# Pi-Can-Hat.net
KiCad netlist of a schematic drawn in EAGLE
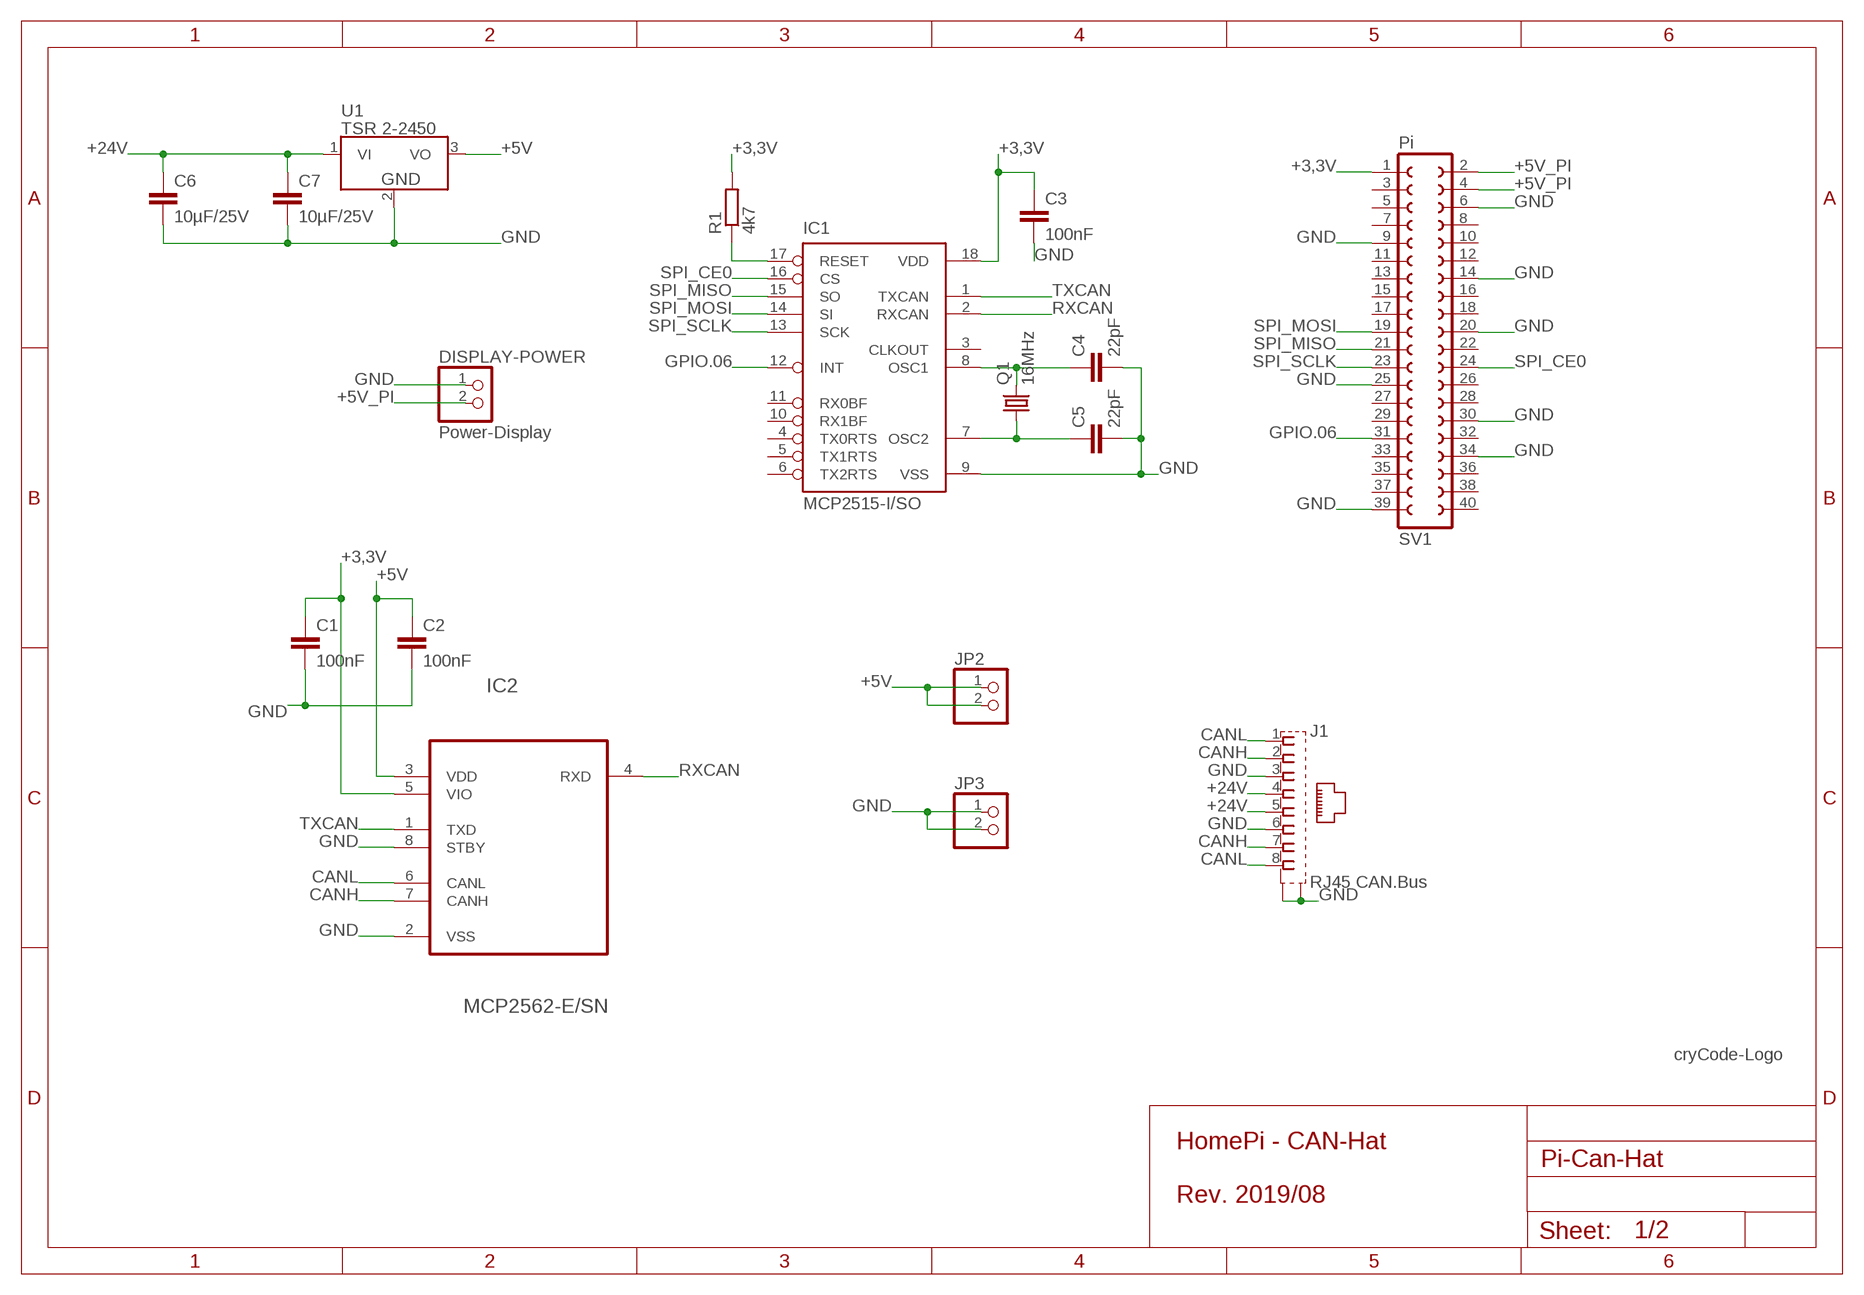
[diagram p0: schematic, sheet 1]
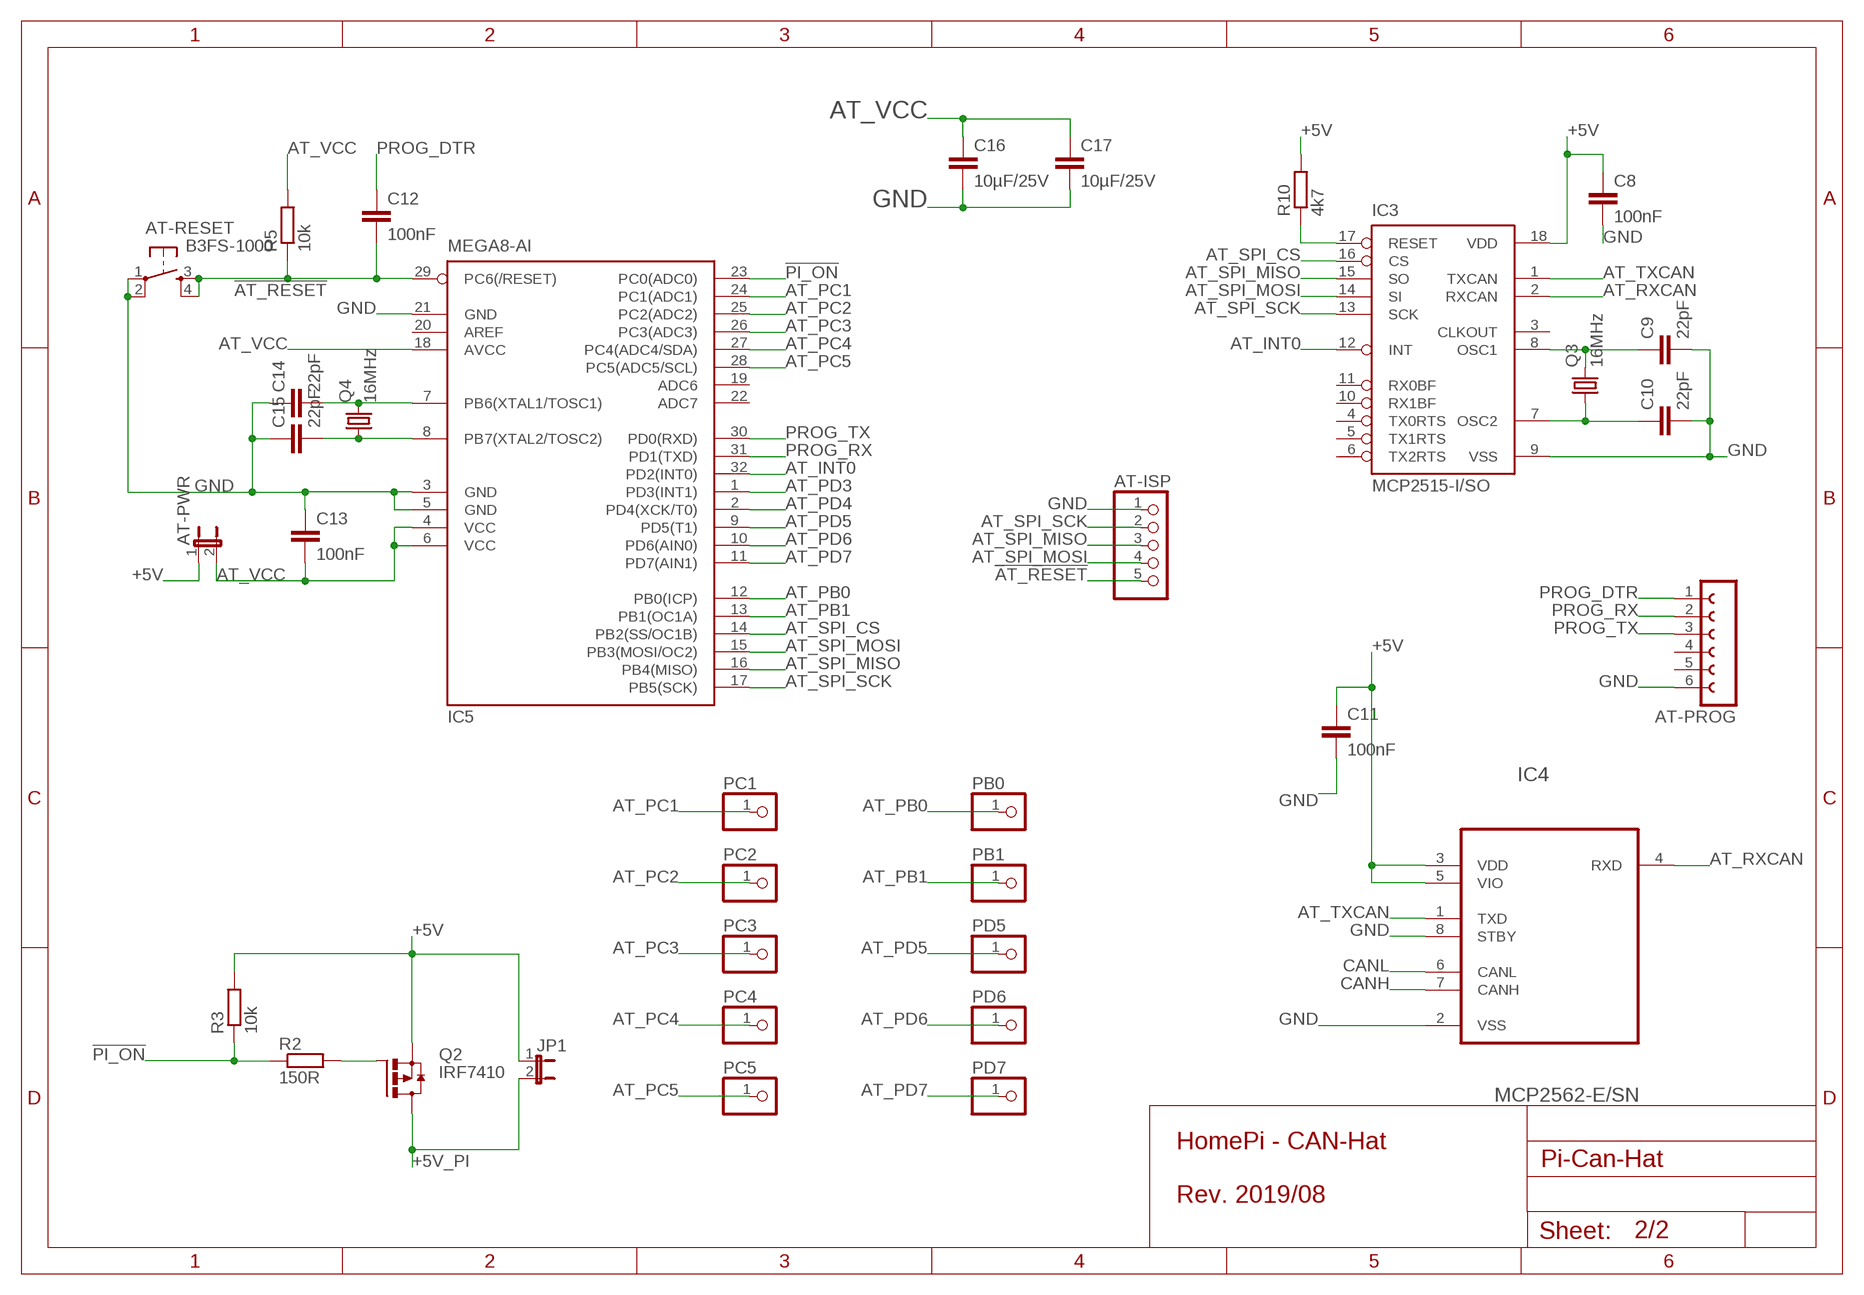
[diagram p1: schematic, sheet 2]

(export (version "E")
  (design (tool "Eeschema 10.0.6"))
  (components
    (comp (ref "AT-ISP")
      (value "PINHD-1X5")
      (footprint "eagle-import:1X05")
      (libsource (lib "eagle-import") (part "PINHD-1X5"))
    )
    (comp (ref "AT-PROG")
      (value "FE06W")
      (footprint "eagle-import:FE06W")
      (libsource (lib "eagle-import") (part "FE06W"))
    )
    (comp (ref "AT-PWR")
      (value "JP1E")
      (footprint "eagle-import:JP1")
      (libsource (lib "eagle-import") (part "JP1E"))
    )
    (comp (ref "AT-RESET")
      (value "B3FS-1000")
      (footprint "eagle-import:B3FS-1000")
      (libsource (lib "eagle-import") (part "B3FS-1000"))
    )
    (comp (ref "C8")
      (value "100nF")
      (footprint "eagle-import:C1206")
      (libsource (lib "eagle-import") (part "C-EUC1206"))
    )
    (comp (ref "C9")
      (value "22pF")
      (footprint "eagle-import:C1206")
      (libsource (lib "eagle-import") (part "C-EUC1206"))
    )
    (comp (ref "C10")
      (value "22pF")
      (footprint "eagle-import:C1206")
      (libsource (lib "eagle-import") (part "C-EUC1206"))
    )
    (comp (ref "C11")
      (value "100nF")
      (footprint "eagle-import:C1206")
      (libsource (lib "eagle-import") (part "C-EUC1206"))
    )
    (comp (ref "C12")
      (value "100nF")
      (footprint "eagle-import:C1206")
      (libsource (lib "eagle-import") (part "C-EUC1206"))
    )
    (comp (ref "C13")
      (value "100nF")
      (footprint "eagle-import:C1206")
      (libsource (lib "eagle-import") (part "C-EUC1206"))
    )
    (comp (ref "C14")
      (value "22pF")
      (footprint "eagle-import:C1206")
      (libsource (lib "eagle-import") (part "C-EUC1206"))
    )
    (comp (ref "C15")
      (value "22pF")
      (footprint "eagle-import:C1206")
      (libsource (lib "eagle-import") (part "C-EUC1206"))
    )
    (comp (ref "C16")
      (value "10µF/25V")
      (footprint "eagle-import:C1206")
      (libsource (lib "eagle-import") (part "C-EUC1206"))
    )
    (comp (ref "C17")
      (value "10µF/25V")
      (footprint "eagle-import:C1206")
      (libsource (lib "eagle-import") (part "C-EUC1206"))
    )
    (comp (ref "IC3")
      (value "MCP2515-I/SO")
      (footprint "eagle-import:SO18L")
      (libsource (lib "eagle-import") (part "MCP2515-I/SO"))
    )
    (comp (ref "IC4")
      (value "MCP2562-E/SN")
      (footprint "eagle-import:SO08")
      (libsource (lib "eagle-import") (part "MCP2562-E/SN"))
    )
    (comp (ref "IC5")
      (value "MEGA8-AI")
      (footprint "eagle-import:TQFP32-08")
      (fields (field (name "MPN") "ATMEGA8-16AU"))
      (libsource (lib "eagle-import") (part "MEGA8-AI"))
    )
    (comp (ref "JP1")
      (value "JP1E")
      (footprint "eagle-import:JP1")
      (libsource (lib "eagle-import") (part "JP1E"))
    )
    (comp (ref "PB0")
      (value "PINHD-1X1")
      (footprint "eagle-import:1X01")
      (libsource (lib "eagle-import") (part "PINHD-1X1"))
    )
    (comp (ref "PB1")
      (value "PINHD-1X1")
      (footprint "eagle-import:1X01")
      (libsource (lib "eagle-import") (part "PINHD-1X1"))
    )
    (comp (ref "PC1")
      (value "PINHD-1X1")
      (footprint "eagle-import:1X01")
      (libsource (lib "eagle-import") (part "PINHD-1X1"))
    )
    (comp (ref "PC2")
      (value "PINHD-1X1")
      (footprint "eagle-import:1X01")
      (libsource (lib "eagle-import") (part "PINHD-1X1"))
    )
    (comp (ref "PC3")
      (value "PINHD-1X1")
      (footprint "eagle-import:1X01")
      (libsource (lib "eagle-import") (part "PINHD-1X1"))
    )
    (comp (ref "PC4")
      (value "PINHD-1X1")
      (footprint "eagle-import:1X01")
      (libsource (lib "eagle-import") (part "PINHD-1X1"))
    )
    (comp (ref "PC5")
      (value "PINHD-1X1")
      (footprint "eagle-import:1X01")
      (libsource (lib "eagle-import") (part "PINHD-1X1"))
    )
    (comp (ref "PD5")
      (value "PINHD-1X1")
      (footprint "eagle-import:1X01")
      (libsource (lib "eagle-import") (part "PINHD-1X1"))
    )
    (comp (ref "PD6")
      (value "PINHD-1X1")
      (footprint "eagle-import:1X01")
      (libsource (lib "eagle-import") (part "PINHD-1X1"))
    )
    (comp (ref "PD7")
      (value "PINHD-1X1")
      (footprint "eagle-import:1X01")
      (libsource (lib "eagle-import") (part "PINHD-1X1"))
    )
    (comp (ref "Q2")
      (value "IRF7410")
      (footprint "eagle-import:SO08")
      (libsource (lib "eagle-import") (part "IRF7410"))
    )
    (comp (ref "Q3")
      (value "16MHz")
      (footprint "eagle-import:HC49UP")
      (libsource (lib "eagle-import") (part "CRYSTALHC49UP"))
    )
    (comp (ref "Q4")
      (value "16MHz")
      (footprint "eagle-import:HC49UP")
      (libsource (lib "eagle-import") (part "CRYSTALHC49UP"))
    )
    (comp (ref "R2")
      (value "150R")
      (footprint "eagle-import:R1206")
      (libsource (lib "eagle-import") (part "R-EU_R1206"))
    )
    (comp (ref "R3")
      (value "10k")
      (footprint "eagle-import:R1206")
      (libsource (lib "eagle-import") (part "R-EU_R1206"))
    )
    (comp (ref "R5")
      (value "10k")
      (footprint "eagle-import:R1206")
      (libsource (lib "eagle-import") (part "R-EU_R1206"))
    )
    (comp (ref "R10")
      (value "4k7")
      (footprint "eagle-import:R1206")
      (libsource (lib "eagle-import") (part "R-EU_R1206"))
    )
    (comp (ref "C1")
      (value "100nF")
      (footprint "eagle-import:C1206")
      (libsource (lib "eagle-import") (part "C-EUC1206"))
    )
    (comp (ref "C2")
      (value "100nF")
      (footprint "eagle-import:C1206")
      (libsource (lib "eagle-import") (part "C-EUC1206"))
    )
    (comp (ref "C3")
      (value "100nF")
      (footprint "eagle-import:C1206")
      (libsource (lib "eagle-import") (part "C-EUC1206"))
    )
    (comp (ref "C4")
      (value "22pF")
      (footprint "eagle-import:C1206")
      (libsource (lib "eagle-import") (part "C-EUC1206"))
    )
    (comp (ref "C5")
      (value "22pF")
      (footprint "eagle-import:C1206")
      (libsource (lib "eagle-import") (part "C-EUC1206"))
    )
    (comp (ref "C6")
      (value "10µF/25V")
      (footprint "eagle-import:C1206")
      (libsource (lib "eagle-import") (part "C-EUC1206"))
    )
    (comp (ref "C7")
      (value "10µF/25V")
      (footprint "eagle-import:C1206")
      (libsource (lib "eagle-import") (part "C-EUC1206"))
    )
    (comp (ref "DISPLAY-POWER")
      (value "Power-Display")
      (footprint "eagle-import:1X02_90")
      (libsource (lib "eagle-import") (part "PINHD-1X2/90"))
    )
    (comp (ref "IC1")
      (value "MCP2515-I/SO")
      (footprint "eagle-import:SO18L")
      (libsource (lib "eagle-import") (part "MCP2515-I/SO"))
    )
    (comp (ref "IC2")
      (value "MCP2562-E/SN")
      (footprint "eagle-import:SO08")
      (libsource (lib "eagle-import") (part "MCP2562-E/SN"))
    )
    (comp (ref "J1")
      (value "RJ45 CAN.Bus")
      (footprint "eagle-import:MEBP_8-8G")
      (libsource (lib "eagle-import") (part "555141-1"))
    )
    (comp (ref "JP2")
      (value "PINHD-1X2")
      (footprint "eagle-import:1X02")
      (libsource (lib "eagle-import") (part "PINHD-1X2"))
    )
    (comp (ref "JP3")
      (value "PINHD-1X2")
      (footprint "eagle-import:1X02")
      (libsource (lib "eagle-import") (part "PINHD-1X2"))
    )
    (comp (ref "Q1")
      (value "16MHz")
      (footprint "eagle-import:HC49UP")
      (libsource (lib "eagle-import") (part "CRYSTALHC49UP"))
    )
    (comp (ref "R1")
      (value "4k7")
      (footprint "eagle-import:R1206")
      (libsource (lib "eagle-import") (part "R-EU_R1206"))
    )
    (comp (ref "SV1")
      (value "Pi")
      (footprint "eagle-import:FE20-2")
      (libsource (lib "eagle-import") (part "FE20-2"))
    )
    (comp (ref "U$1")
      (value "LOGO30MM")
      (footprint "eagle-import:30MM")
      (libsource (lib "eagle-import") (part "LOGO30MM"))
    )
    (comp (ref "U1")
      (value "TSR 2-2450")
      (footprint "eagle-import:TSR2")
      (libsource (lib "eagle-import") (part "TSR2-2450"))
    )
  )
  (nets
    (net (code "1") (name "+3,3V") (class "Default")
      (node (ref "C1") (pin "1") (pinfunction "1_1") (pintype "passive"))
      (node (ref "C3") (pin "1") (pinfunction "1_1") (pintype "passive"))
      (node (ref "IC1") (pin "18") (pinfunction "VDD_18") (pintype "power_in"))
      (node (ref "IC2") (pin "5") (pinfunction "VIO_5") (pintype "power_in"))
      (node (ref "R1") (pin "2") (pinfunction "2_2") (pintype "passive"))
      (node (ref "SV1") (pin "1") (pinfunction "1_1") (pintype "passive"))
    )
    (net (code "2") (name "+5V") (class "Default")
      (node (ref "AT-PWR") (pin "1") (pinfunction "1_1") (pintype "passive"))
      (node (ref "C11") (pin "1") (pinfunction "1_1") (pintype "passive"))
      (node (ref "C2") (pin "1") (pinfunction "1_1") (pintype "passive"))
      (node (ref "C8") (pin "1") (pinfunction "1_1") (pintype "passive"))
      (node (ref "IC2") (pin "3") (pinfunction "VDD_3") (pintype "power_in"))
      (node (ref "IC3") (pin "18") (pinfunction "VDD_18") (pintype "power_in"))
      (node (ref "IC4") (pin "3") (pinfunction "VDD_3") (pintype "power_in"))
      (node (ref "IC4") (pin "5") (pinfunction "VIO_5") (pintype "power_in"))
      (node (ref "JP1") (pin "1") (pinfunction "1_1") (pintype "passive"))
      (node (ref "JP2") (pin "1") (pinfunction "1_1") (pintype "passive"))
      (node (ref "JP2") (pin "2") (pinfunction "2_2") (pintype "passive"))
      (node (ref "Q2") (pin "1") (pinfunction "S_1") (pintype "passive"))
      (node (ref "Q2") (pin "2") (pinfunction "S_2") (pintype "passive"))
      (node (ref "Q2") (pin "3") (pinfunction "S_3") (pintype "passive"))
      (node (ref "R10") (pin "2") (pinfunction "2_2") (pintype "passive"))
      (node (ref "R3") (pin "2") (pinfunction "2_2") (pintype "passive"))
      (node (ref "U1") (pin "3") (pinfunction "VO_3") (pintype "power_in"))
    )
    (net (code "3") (name "+5V_PI") (class "Default")
      (node (ref "DISPLAY-POWER") (pin "2") (pinfunction "2_2") (pintype "passive"))
      (node (ref "JP1") (pin "2") (pinfunction "2_2") (pintype "passive"))
      (node (ref "Q2") (pin "5") (pinfunction "D_5") (pintype "passive"))
      (node (ref "Q2") (pin "6") (pinfunction "D_6") (pintype "passive"))
      (node (ref "Q2") (pin "7") (pinfunction "D_7") (pintype "passive"))
      (node (ref "Q2") (pin "8") (pinfunction "D_8") (pintype "passive"))
      (node (ref "SV1") (pin "2") (pinfunction "2_2") (pintype "passive"))
      (node (ref "SV1") (pin "4") (pinfunction "4_4") (pintype "passive"))
    )
    (net (code "4") (name "+24V") (class "Default")
      (node (ref "C6") (pin "1") (pinfunction "1_1") (pintype "passive"))
      (node (ref "C7") (pin "1") (pinfunction "1_1") (pintype "passive"))
      (node (ref "J1") (pin "4") (pinfunction "4_4") (pintype "passive"))
      (node (ref "J1") (pin "5") (pinfunction "5_5") (pintype "passive"))
      (node (ref "U1") (pin "1") (pinfunction "VI_1") (pintype "power_in"))
    )
    (net (code "5") (name "AT_INT0") (class "Default")
      (node (ref "IC3") (pin "12") (pinfunction "INT_12") (pintype "output"))
      (node (ref "IC5") (pin "32") (pinfunction "PD2(INT0)_32") (pintype "bidirectional"))
    )
    (net (code "6") (name "AT_PB0") (class "Default")
      (node (ref "IC5") (pin "12") (pinfunction "PB0(ICP)_12") (pintype "bidirectional"))
      (node (ref "PB0") (pin "1") (pinfunction "1_1") (pintype "passive"))
    )
    (net (code "7") (name "AT_PB1") (class "Default")
      (node (ref "IC5") (pin "13") (pinfunction "PB1(OC1A)_13") (pintype "bidirectional"))
      (node (ref "PB1") (pin "1") (pinfunction "1_1") (pintype "passive"))
    )
    (net (code "8") (name "AT_PC1") (class "Default")
      (node (ref "IC5") (pin "24") (pinfunction "PC1(ADC1)_24") (pintype "bidirectional"))
      (node (ref "PC1") (pin "1") (pinfunction "1_1") (pintype "passive"))
    )
    (net (code "9") (name "AT_PC2") (class "Default")
      (node (ref "IC5") (pin "25") (pinfunction "PC2(ADC2)_25") (pintype "bidirectional"))
      (node (ref "PC2") (pin "1") (pinfunction "1_1") (pintype "passive"))
    )
    (net (code "10") (name "AT_PC3") (class "Default")
      (node (ref "IC5") (pin "26") (pinfunction "PC3(ADC3)_26") (pintype "bidirectional"))
      (node (ref "PC3") (pin "1") (pinfunction "1_1") (pintype "passive"))
    )
    (net (code "11") (name "AT_PC4") (class "Default")
      (node (ref "IC5") (pin "27") (pinfunction "PC4(ADC4/SDA)_27") (pintype "bidirectional"))
      (node (ref "PC4") (pin "1") (pinfunction "1_1") (pintype "passive"))
    )
    (net (code "12") (name "AT_PC5") (class "Default")
      (node (ref "IC5") (pin "28") (pinfunction "PC5(ADC5/SCL)_28") (pintype "bidirectional"))
      (node (ref "PC5") (pin "1") (pinfunction "1_1") (pintype "passive"))
    )
    (net (code "13") (name "AT_PD3") (class "Default")
      (node (ref "IC5") (pin "1") (pinfunction "PD3(INT1)_1") (pintype "bidirectional"))
    )
    (net (code "14") (name "AT_PD4") (class "Default")
      (node (ref "IC5") (pin "2") (pinfunction "PD4(XCK/T0)_2") (pintype "bidirectional"))
    )
    (net (code "15") (name "AT_PD5") (class "Default")
      (node (ref "IC5") (pin "9") (pinfunction "PD5(T1)_9") (pintype "bidirectional"))
      (node (ref "PD5") (pin "1") (pinfunction "1_1") (pintype "passive"))
    )
    (net (code "16") (name "AT_PD6") (class "Default")
      (node (ref "IC5") (pin "10") (pinfunction "PD6(AIN0)_10") (pintype "bidirectional"))
      (node (ref "PD6") (pin "1") (pinfunction "1_1") (pintype "passive"))
    )
    (net (code "17") (name "AT_PD7") (class "Default")
      (node (ref "IC5") (pin "11") (pinfunction "PD7(AIN1)_11") (pintype "bidirectional"))
      (node (ref "PD7") (pin "1") (pinfunction "1_1") (pintype "passive"))
    )
    (net (code "18") (name "AT_RXCAN") (class "Default")
      (node (ref "IC3") (pin "2") (pinfunction "RXCAN_2") (pintype "input"))
      (node (ref "IC4") (pin "4") (pinfunction "RXD_4") (pintype "output"))
    )
    (net (code "19") (name "AT_SPI_CS") (class "Default")
      (node (ref "IC3") (pin "16") (pinfunction "CS_16") (pintype "input"))
      (node (ref "IC5") (pin "14") (pinfunction "PB2(SS/OC1B)_14") (pintype "bidirectional"))
    )
    (net (code "20") (name "AT_SPI_MISO") (class "Default")
      (node (ref "AT-ISP") (pin "3") (pinfunction "3_3") (pintype "passive"))
      (node (ref "IC3") (pin "15") (pinfunction "SO_15") (pintype "output"))
      (node (ref "IC5") (pin "16") (pinfunction "PB4(MISO)_16") (pintype "bidirectional"))
    )
    (net (code "21") (name "AT_SPI_MOSI") (class "Default")
      (node (ref "AT-ISP") (pin "4") (pinfunction "4_4") (pintype "passive"))
      (node (ref "IC3") (pin "14") (pinfunction "SI_14") (pintype "input"))
      (node (ref "IC5") (pin "15") (pinfunction "PB3(MOSI/OC2)_15") (pintype "bidirectional"))
    )
    (net (code "22") (name "AT_SPI_SCK") (class "Default")
      (node (ref "AT-ISP") (pin "2") (pinfunction "2_2") (pintype "passive"))
      (node (ref "IC3") (pin "13") (pinfunction "SCK_13") (pintype "input"))
      (node (ref "IC5") (pin "17") (pinfunction "PB5(SCK)_17") (pintype "bidirectional"))
    )
    (net (code "23") (name "AT_TXCAN") (class "Default")
      (node (ref "IC3") (pin "1") (pinfunction "TXCAN_1") (pintype "output"))
      (node (ref "IC4") (pin "1") (pinfunction "TXD_1") (pintype "input"))
    )
    (net (code "24") (name "AT_VCC") (class "Default")
      (node (ref "AT-PWR") (pin "2") (pinfunction "2_2") (pintype "passive"))
      (node (ref "C13") (pin "2") (pinfunction "2_2") (pintype "passive"))
      (node (ref "C16") (pin "1") (pinfunction "1_1") (pintype "passive"))
      (node (ref "C17") (pin "1") (pinfunction "1_1") (pintype "passive"))
      (node (ref "IC5") (pin "18") (pinfunction "AVCC_18") (pintype "power_in"))
      (node (ref "IC5") (pin "4") (pinfunction "VCC_4") (pintype "power_in"))
      (node (ref "IC5") (pin "6") (pinfunction "VCC_6") (pintype "power_in"))
      (node (ref "R5") (pin "2") (pinfunction "2_2") (pintype "passive"))
    )
    (net (code "25") (name "CANH") (class "Default")
      (node (ref "IC2") (pin "7") (pinfunction "CANH_7") (pintype "bidirectional"))
      (node (ref "IC4") (pin "7") (pinfunction "CANH_7") (pintype "bidirectional"))
      (node (ref "J1") (pin "2") (pinfunction "2_2") (pintype "passive"))
      (node (ref "J1") (pin "7") (pinfunction "7_7") (pintype "passive"))
    )
    (net (code "26") (name "CANL") (class "Default")
      (node (ref "IC2") (pin "6") (pinfunction "CANL_6") (pintype "bidirectional"))
      (node (ref "IC4") (pin "6") (pinfunction "CANL_6") (pintype "bidirectional"))
      (node (ref "J1") (pin "1") (pinfunction "1_1") (pintype "passive"))
      (node (ref "J1") (pin "8") (pinfunction "8_8") (pintype "passive"))
    )
    (net (code "27") (name "GND") (class "Default")
      (node (ref "AT-ISP") (pin "1") (pinfunction "1_1") (pintype "passive"))
      (node (ref "AT-PROG") (pin "6") (pinfunction "6_6") (pintype "passive"))
      (node (ref "AT-RESET") (pin "1") (pinfunction "P_1") (pintype "passive"))
      (node (ref "AT-RESET") (pin "2") (pinfunction "P1_2") (pintype "passive"))
      (node (ref "C1") (pin "2") (pinfunction "2_2") (pintype "passive"))
      (node (ref "C10") (pin "2") (pinfunction "2_2") (pintype "passive"))
      (node (ref "C11") (pin "2") (pinfunction "2_2") (pintype "passive"))
      (node (ref "C13") (pin "1") (pinfunction "1_1") (pintype "passive"))
      (node (ref "C14") (pin "1") (pinfunction "1_1") (pintype "passive"))
      (node (ref "C15") (pin "1") (pinfunction "1_1") (pintype "passive"))
      (node (ref "C16") (pin "2") (pinfunction "2_2") (pintype "passive"))
      (node (ref "C17") (pin "2") (pinfunction "2_2") (pintype "passive"))
      (node (ref "C2") (pin "2") (pinfunction "2_2") (pintype "passive"))
      (node (ref "C3") (pin "2") (pinfunction "2_2") (pintype "passive"))
      (node (ref "C4") (pin "2") (pinfunction "2_2") (pintype "passive"))
      (node (ref "C5") (pin "2") (pinfunction "2_2") (pintype "passive"))
      (node (ref "C6") (pin "2") (pinfunction "2_2") (pintype "passive"))
      (node (ref "C7") (pin "2") (pinfunction "2_2") (pintype "passive"))
      (node (ref "C8") (pin "2") (pinfunction "2_2") (pintype "passive"))
      (node (ref "C9") (pin "2") (pinfunction "2_2") (pintype "passive"))
      (node (ref "DISPLAY-POWER") (pin "1") (pinfunction "1_1") (pintype "passive"))
      (node (ref "IC1") (pin "9") (pinfunction "VSS_9") (pintype "power_in"))
      (node (ref "IC2") (pin "2") (pinfunction "VSS_2") (pintype "power_in"))
      (node (ref "IC2") (pin "8") (pinfunction "STBY_8") (pintype "input"))
      (node (ref "IC3") (pin "9") (pinfunction "VSS_9") (pintype "power_in"))
      (node (ref "IC4") (pin "2") (pinfunction "VSS_2") (pintype "power_in"))
      (node (ref "IC4") (pin "8") (pinfunction "STBY_8") (pintype "input"))
      (node (ref "IC5") (pin "21") (pinfunction "GND_21") (pintype "power_in"))
      (node (ref "IC5") (pin "3") (pinfunction "GND_3") (pintype "power_in"))
      (node (ref "IC5") (pin "5") (pinfunction "GND_5") (pintype "power_in"))
      (node (ref "J1") (pin "3") (pinfunction "3_3") (pintype "passive"))
      (node (ref "J1") (pin "6") (pinfunction "6_6") (pintype "passive"))
      (node (ref "J1") (pin "G1") (pinfunction "S1_G1") (pintype "passive"))
      (node (ref "J1") (pin "G2") (pinfunction "S2_G2") (pintype "passive"))
      (node (ref "JP3") (pin "1") (pinfunction "1_1") (pintype "passive"))
      (node (ref "JP3") (pin "2") (pinfunction "2_2") (pintype "passive"))
      (node (ref "SV1") (pin "14") (pinfunction "14_14") (pintype "passive"))
      (node (ref "SV1") (pin "20") (pinfunction "20_20") (pintype "passive"))
      (node (ref "SV1") (pin "25") (pinfunction "25_25") (pintype "passive"))
      (node (ref "SV1") (pin "30") (pinfunction "30_30") (pintype "passive"))
      (node (ref "SV1") (pin "34") (pinfunction "34_34") (pintype "passive"))
      (node (ref "SV1") (pin "39") (pinfunction "39_39") (pintype "passive"))
      (node (ref "SV1") (pin "6") (pinfunction "6_6") (pintype "passive"))
      (node (ref "SV1") (pin "9") (pinfunction "9_9") (pintype "passive"))
      (node (ref "U1") (pin "2") (pinfunction "GND_2") (pintype "power_in"))
    )
    (net (code "28") (name "GPIO.06") (class "Default")
      (node (ref "IC1") (pin "12") (pinfunction "INT_12") (pintype "output"))
      (node (ref "SV1") (pin "31") (pinfunction "31_31") (pintype "passive"))
    )
    (net (code "29") (name "Net-(IC1-OSC1)") (class "Default")
      (node (ref "C4") (pin "1") (pinfunction "1_1") (pintype "passive"))
      (node (ref "IC1") (pin "8") (pinfunction "OSC1_8") (pintype "input"))
      (node (ref "Q1") (pin "2") (pinfunction "2_2") (pintype "passive"))
    )
    (net (code "30") (name "Net-(IC1-OSC2)") (class "Default")
      (node (ref "C5") (pin "1") (pinfunction "1_1") (pintype "passive"))
      (node (ref "IC1") (pin "7") (pinfunction "OSC2_7") (pintype "output"))
      (node (ref "Q1") (pin "1") (pinfunction "1_1") (pintype "passive"))
    )
    (net (code "31") (name "Net-(IC1-RESET)") (class "Default")
      (node (ref "IC1") (pin "17") (pinfunction "RESET_17") (pintype "input"))
      (node (ref "R1") (pin "1") (pinfunction "1_1") (pintype "passive"))
    )
    (net (code "32") (name "Net-(IC3-OSC1)") (class "Default")
      (node (ref "C9") (pin "1") (pinfunction "1_1") (pintype "passive"))
      (node (ref "IC3") (pin "8") (pinfunction "OSC1_8") (pintype "input"))
      (node (ref "Q3") (pin "2") (pinfunction "2_2") (pintype "passive"))
    )
    (net (code "33") (name "Net-(IC3-OSC2)") (class "Default")
      (node (ref "C10") (pin "1") (pinfunction "1_1") (pintype "passive"))
      (node (ref "IC3") (pin "7") (pinfunction "OSC2_7") (pintype "output"))
      (node (ref "Q3") (pin "1") (pinfunction "1_1") (pintype "passive"))
    )
    (net (code "34") (name "Net-(IC3-RESET)") (class "Default")
      (node (ref "IC3") (pin "17") (pinfunction "RESET_17") (pintype "input"))
      (node (ref "R10") (pin "1") (pinfunction "1_1") (pintype "passive"))
    )
    (net (code "35") (name "Net-(IC5-PB6(XTAL1{slash}TOSC1))") (class "Default")
      (node (ref "C14") (pin "2") (pinfunction "2_2") (pintype "passive"))
      (node (ref "IC5") (pin "7") (pinfunction "PB6(XTAL1/TOSC1)_7") (pintype "bidirectional"))
      (node (ref "Q4") (pin "2") (pinfunction "2_2") (pintype "passive"))
    )
    (net (code "36") (name "Net-(IC5-PB7(XTAL2{slash}TOSC2))") (class "Default")
      (node (ref "C15") (pin "2") (pinfunction "2_2") (pintype "passive"))
      (node (ref "IC5") (pin "8") (pinfunction "PB7(XTAL2/TOSC2)_8") (pintype "bidirectional"))
      (node (ref "Q4") (pin "1") (pinfunction "1_1") (pintype "passive"))
    )
    (net (code "37") (name "Net-(Q2-G)") (class "Default")
      (node (ref "Q2") (pin "4") (pinfunction "G_4") (pintype "passive"))
      (node (ref "R2") (pin "2") (pinfunction "2_2") (pintype "passive"))
    )
    (net (code "38") (name "PROG_DTR") (class "Default")
      (node (ref "AT-PROG") (pin "1") (pinfunction "1_1") (pintype "passive"))
      (node (ref "C12") (pin "1") (pinfunction "1_1") (pintype "passive"))
    )
    (net (code "39") (name "PROG_RX") (class "Default")
      (node (ref "AT-PROG") (pin "2") (pinfunction "2_2") (pintype "passive"))
      (node (ref "IC5") (pin "31") (pinfunction "PD1(TXD)_31") (pintype "bidirectional"))
    )
    (net (code "40") (name "PROG_TX") (class "Default")
      (node (ref "AT-PROG") (pin "3") (pinfunction "3_3") (pintype "passive"))
      (node (ref "IC5") (pin "30") (pinfunction "PD0(RXD)_30") (pintype "bidirectional"))
    )
    (net (code "41") (name "RXCAN") (class "Default")
      (node (ref "IC1") (pin "2") (pinfunction "RXCAN_2") (pintype "input"))
      (node (ref "IC2") (pin "4") (pinfunction "RXD_4") (pintype "output"))
    )
    (net (code "42") (name "SPI_CE0") (class "Default")
      (node (ref "IC1") (pin "16") (pinfunction "CS_16") (pintype "input"))
      (node (ref "SV1") (pin "24") (pinfunction "24_24") (pintype "passive"))
    )
    (net (code "43") (name "SPI_MISO") (class "Default")
      (node (ref "IC1") (pin "15") (pinfunction "SO_15") (pintype "output"))
      (node (ref "SV1") (pin "21") (pinfunction "21_21") (pintype "passive"))
    )
    (net (code "44") (name "SPI_MOSI") (class "Default")
      (node (ref "IC1") (pin "14") (pinfunction "SI_14") (pintype "input"))
      (node (ref "SV1") (pin "19") (pinfunction "19_19") (pintype "passive"))
    )
    (net (code "45") (name "SPI_SCLK") (class "Default")
      (node (ref "IC1") (pin "13") (pinfunction "SCK_13") (pintype "input"))
      (node (ref "SV1") (pin "23") (pinfunction "23_23") (pintype "passive"))
    )
    (net (code "46") (name "TXCAN") (class "Default")
      (node (ref "IC1") (pin "1") (pinfunction "TXCAN_1") (pintype "output"))
      (node (ref "IC2") (pin "1") (pinfunction "TXD_1") (pintype "input"))
    )
    (net (code "47") (name "unconnected-(AT-PROG-Pad4)") (class "Default")
      (node (ref "AT-PROG") (pin "4") (pinfunction "4_4") (pintype "passive"))
    )
    (net (code "48") (name "unconnected-(AT-PROG-Pad5)") (class "Default")
      (node (ref "AT-PROG") (pin "5") (pinfunction "5_5") (pintype "passive"))
    )
    (net (code "49") (name "unconnected-(IC1-CLKOUT-Pad3)") (class "Default")
      (node (ref "IC1") (pin "3") (pinfunction "CLKOUT_3") (pintype "output"))
    )
    (net (code "50") (name "unconnected-(IC1-RX0BF-Pad11)") (class "Default")
      (node (ref "IC1") (pin "11") (pinfunction "RX0BF_11") (pintype "output"))
    )
    (net (code "51") (name "unconnected-(IC1-RX1BF-Pad10)") (class "Default")
      (node (ref "IC1") (pin "10") (pinfunction "RX1BF_10") (pintype "output"))
    )
    (net (code "52") (name "unconnected-(IC1-TX0RTS-Pad4)") (class "Default")
      (node (ref "IC1") (pin "4") (pinfunction "TX0RTS_4") (pintype "input"))
    )
    (net (code "53") (name "unconnected-(IC1-TX1RTS-Pad5)") (class "Default")
      (node (ref "IC1") (pin "5") (pinfunction "TX1RTS_5") (pintype "input"))
    )
    (net (code "54") (name "unconnected-(IC1-TX2RTS-Pad6)") (class "Default")
      (node (ref "IC1") (pin "6") (pinfunction "TX2RTS_6") (pintype "input"))
    )
    (net (code "55") (name "unconnected-(IC3-CLKOUT-Pad3)") (class "Default")
      (node (ref "IC3") (pin "3") (pinfunction "CLKOUT_3") (pintype "output"))
    )
    (net (code "56") (name "unconnected-(IC3-RX0BF-Pad11)") (class "Default")
      (node (ref "IC3") (pin "11") (pinfunction "RX0BF_11") (pintype "output"))
    )
    (net (code "57") (name "unconnected-(IC3-RX1BF-Pad10)") (class "Default")
      (node (ref "IC3") (pin "10") (pinfunction "RX1BF_10") (pintype "output"))
    )
    (net (code "58") (name "unconnected-(IC3-TX0RTS-Pad4)") (class "Default")
      (node (ref "IC3") (pin "4") (pinfunction "TX0RTS_4") (pintype "input"))
    )
    (net (code "59") (name "unconnected-(IC3-TX1RTS-Pad5)") (class "Default")
      (node (ref "IC3") (pin "5") (pinfunction "TX1RTS_5") (pintype "input"))
    )
    (net (code "60") (name "unconnected-(IC3-TX2RTS-Pad6)") (class "Default")
      (node (ref "IC3") (pin "6") (pinfunction "TX2RTS_6") (pintype "input"))
    )
    (net (code "61") (name "unconnected-(IC5-ADC6-Pad19)") (class "Default")
      (node (ref "IC5") (pin "19") (pinfunction "ADC6_19") (pintype "bidirectional"))
    )
    (net (code "62") (name "unconnected-(IC5-ADC7-Pad22)") (class "Default")
      (node (ref "IC5") (pin "22") (pinfunction "ADC7_22") (pintype "bidirectional"))
    )
    (net (code "63") (name "unconnected-(IC5-AREF-Pad20)") (class "Default")
      (node (ref "IC5") (pin "20") (pinfunction "AREF_20") (pintype "passive"))
    )
    (net (code "64") (name "unconnected-(SV1-Pad3)") (class "Default")
      (node (ref "SV1") (pin "3") (pinfunction "3_3") (pintype "passive"))
    )
    (net (code "65") (name "unconnected-(SV1-Pad5)") (class "Default")
      (node (ref "SV1") (pin "5") (pinfunction "5_5") (pintype "passive"))
    )
    (net (code "66") (name "unconnected-(SV1-Pad7)") (class "Default")
      (node (ref "SV1") (pin "7") (pinfunction "7_7") (pintype "passive"))
    )
    (net (code "67") (name "unconnected-(SV1-Pad8)") (class "Default")
      (node (ref "SV1") (pin "8") (pinfunction "8_8") (pintype "passive"))
    )
    (net (code "68") (name "unconnected-(SV1-Pad10)") (class "Default")
      (node (ref "SV1") (pin "10") (pinfunction "10_10") (pintype "passive"))
    )
    (net (code "69") (name "unconnected-(SV1-Pad11)") (class "Default")
      (node (ref "SV1") (pin "11") (pinfunction "11_11") (pintype "passive"))
    )
    (net (code "70") (name "unconnected-(SV1-Pad12)") (class "Default")
      (node (ref "SV1") (pin "12") (pinfunction "12_12") (pintype "passive"))
    )
    (net (code "71") (name "unconnected-(SV1-Pad13)") (class "Default")
      (node (ref "SV1") (pin "13") (pinfunction "13_13") (pintype "passive"))
    )
    (net (code "72") (name "unconnected-(SV1-Pad15)") (class "Default")
      (node (ref "SV1") (pin "15") (pinfunction "15_15") (pintype "passive"))
    )
    (net (code "73") (name "unconnected-(SV1-Pad16)") (class "Default")
      (node (ref "SV1") (pin "16") (pinfunction "16_16") (pintype "passive"))
    )
    (net (code "74") (name "unconnected-(SV1-Pad17)") (class "Default")
      (node (ref "SV1") (pin "17") (pinfunction "17_17") (pintype "passive"))
    )
    (net (code "75") (name "unconnected-(SV1-Pad18)") (class "Default")
      (node (ref "SV1") (pin "18") (pinfunction "18_18") (pintype "passive"))
    )
    (net (code "76") (name "unconnected-(SV1-Pad22)") (class "Default")
      (node (ref "SV1") (pin "22") (pinfunction "22_22") (pintype "passive"))
    )
    (net (code "77") (name "unconnected-(SV1-Pad26)") (class "Default")
      (node (ref "SV1") (pin "26") (pinfunction "26_26") (pintype "passive"))
    )
    (net (code "78") (name "unconnected-(SV1-Pad27)") (class "Default")
      (node (ref "SV1") (pin "27") (pinfunction "27_27") (pintype "passive"))
    )
    (net (code "79") (name "unconnected-(SV1-Pad28)") (class "Default")
      (node (ref "SV1") (pin "28") (pinfunction "28_28") (pintype "passive"))
    )
    (net (code "80") (name "unconnected-(SV1-Pad29)") (class "Default")
      (node (ref "SV1") (pin "29") (pinfunction "29_29") (pintype "passive"))
    )
    (net (code "81") (name "unconnected-(SV1-Pad32)") (class "Default")
      (node (ref "SV1") (pin "32") (pinfunction "32_32") (pintype "passive"))
    )
    (net (code "82") (name "unconnected-(SV1-Pad33)") (class "Default")
      (node (ref "SV1") (pin "33") (pinfunction "33_33") (pintype "passive"))
    )
    (net (code "83") (name "unconnected-(SV1-Pad35)") (class "Default")
      (node (ref "SV1") (pin "35") (pinfunction "35_35") (pintype "passive"))
    )
    (net (code "84") (name "unconnected-(SV1-Pad36)") (class "Default")
      (node (ref "SV1") (pin "36") (pinfunction "36_36") (pintype "passive"))
    )
    (net (code "85") (name "unconnected-(SV1-Pad37)") (class "Default")
      (node (ref "SV1") (pin "37") (pinfunction "37_37") (pintype "passive"))
    )
    (net (code "86") (name "unconnected-(SV1-Pad38)") (class "Default")
      (node (ref "SV1") (pin "38") (pinfunction "38_38") (pintype "passive"))
    )
    (net (code "87") (name "unconnected-(SV1-Pad40)") (class "Default")
      (node (ref "SV1") (pin "40") (pinfunction "40_40") (pintype "passive"))
    )
    (net (code "88") (name "~{AT_RESET}") (class "Default")
      (node (ref "AT-ISP") (pin "5") (pinfunction "5_5") (pintype "passive"))
      (node (ref "AT-RESET") (pin "3") (pinfunction "S_3") (pintype "passive"))
      (node (ref "AT-RESET") (pin "4") (pinfunction "S1_4") (pintype "passive"))
      (node (ref "C12") (pin "2") (pinfunction "2_2") (pintype "passive"))
      (node (ref "IC5") (pin "29") (pinfunction "PC6(/RESET)_29") (pintype "bidirectional"))
      (node (ref "R5") (pin "1") (pinfunction "1_1") (pintype "passive"))
    )
    (net (code "89") (name "~{PI_ON}") (class "Default")
      (node (ref "IC5") (pin "23") (pinfunction "PC0(ADC0)_23") (pintype "bidirectional"))
      (node (ref "R2") (pin "1") (pinfunction "1_1") (pintype "passive"))
      (node (ref "R3") (pin "1") (pinfunction "1_1") (pintype "passive"))
    )
  )
)
